# TFT_4_0-inch_OTM8009A_Sch.net
KiCad netlist of a schematic drawn in Altium Designer
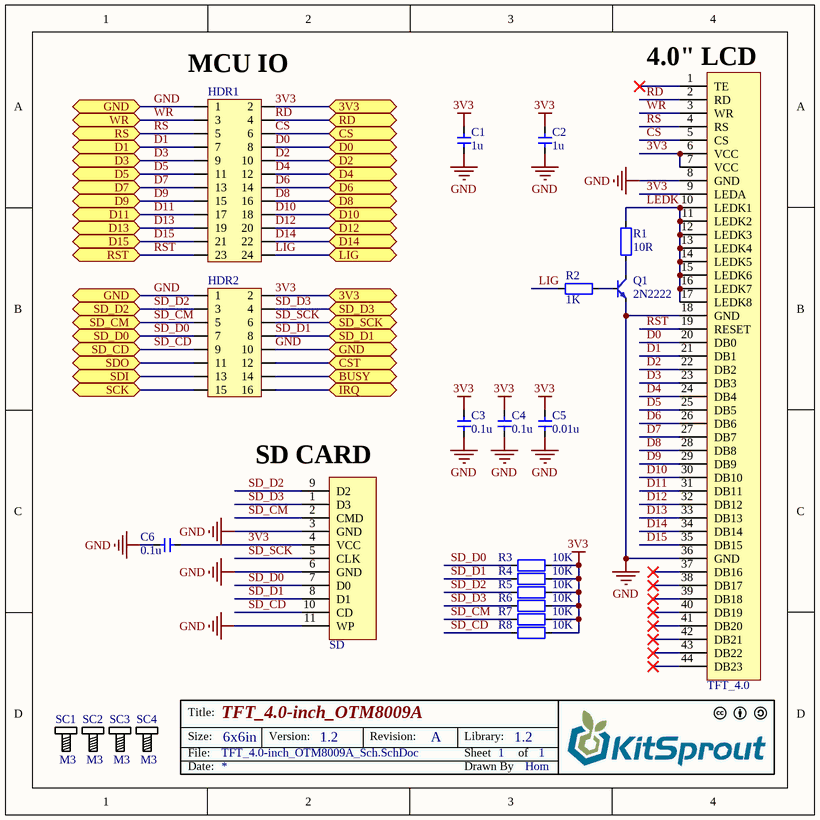
[diagram p0: TFT_4.0-inch_OTM8009A_Sch.SchDoc]

(export (version "E")
  (design (tool "Eeschema 10.0.6"))
  (components
    (comp (ref "C1")
      (value "1u")
      (footprint "PCB_PassiveCap:CAP_0603")
      (description "Capacitor")
      (fields (field (name "Comment") "Cap_0603"))
      (libsource (lib "SCH_Passive") (part "Cap_0603"))
    )
    (comp (ref "C2")
      (value "1u")
      (footprint "PCB_PassiveCap:CAP_0603")
      (description "Capacitor")
      (fields (field (name "Comment") "Cap_0603"))
      (libsource (lib "SCH_Passive") (part "Cap_0603"))
    )
    (comp (ref "C3")
      (value "0.1u")
      (footprint "PCB_PassiveCap:CAP_0603")
      (description "Capacitor")
      (fields (field (name "Comment") "Cap_0603"))
      (libsource (lib "SCH_Passive") (part "Cap_0603"))
    )
    (comp (ref "C4")
      (value "0.1u")
      (footprint "PCB_PassiveCap:CAP_0603")
      (description "Capacitor")
      (fields (field (name "Comment") "Cap_0603"))
      (libsource (lib "SCH_Passive") (part "Cap_0603"))
    )
    (comp (ref "C5")
      (value "0.01u")
      (footprint "PCB_PassiveCap:CAP_0603")
      (description "Capacitor")
      (fields (field (name "Comment") "Cap_0603"))
      (libsource (lib "SCH_Passive") (part "Cap_0603"))
    )
    (comp (ref "C6")
      (value "0.1u")
      (footprint "PCB_PassiveCap:CAP_0603")
      (description "Capacitor")
      (fields (field (name "Comment") "Cap_0603"))
      (libsource (lib "SCH_Passive") (part "Cap_0603"))
    )
    (comp (ref "HDR1")
      (value "HDR2x12_2.54")
      (footprint "PCB_ConnectorHDR:HDR2X12_2.54_180F")
      (description "Header")
      (libsource (lib "SCH_ConnectorHDR") (part "HDR2x12_2.54"))
    )
    (comp (ref "HDR2")
      (value "HDR2x8_2.54")
      (footprint "PCB_ConnectorHDR:HDR2X8_2.54_180F")
      (description "Header")
      (libsource (lib "SCH_ConnectorHDR") (part "HDR2x8_2.54"))
    )
    (comp (ref "Q1")
      (value "BJT_NPN")
      (footprint "PCB_IntegratedCircuit:SOT23-3")
      (description "Transistor")
      (fields (field (name "ALTIUM_UNNAMED_1") "2N2222"))
      (libsource (lib "SCH_Active") (part "BJT_NPN"))
    )
    (comp (ref "R1")
      (value "10R")
      (footprint "PCB_PassiveRes:RES_0603")
      (description "Resistor")
      (fields (field (name "Comment") "Res_0603"))
      (libsource (lib "SCH_Passive") (part "Res_0603"))
    )
    (comp (ref "R2")
      (value "1K")
      (footprint "PCB_PassiveRes:RES_0603")
      (description "Resistor")
      (fields (field (name "Comment") "Res_0603"))
      (libsource (lib "") (part "Res_0603_1"))
    )
    (comp (ref "R3")
      (value "10K")
      (footprint "PCB_PassiveRes:RES_0603")
      (description "Resistor")
      (fields (field (name "Comment") "Res_0603"))
      (libsource (lib "") (part "Res_0603_1"))
    )
    (comp (ref "R4")
      (value "10K")
      (footprint "PCB_PassiveRes:RES_0603")
      (description "Resistor")
      (fields (field (name "Comment") "Res_0603"))
      (libsource (lib "") (part "Res_0603_1"))
    )
    (comp (ref "R5")
      (value "10K")
      (footprint "PCB_PassiveRes:RES_0603")
      (description "Resistor")
      (fields (field (name "Comment") "Res_0603"))
      (libsource (lib "") (part "Res_0603_1"))
    )
    (comp (ref "R6")
      (value "10K")
      (footprint "PCB_PassiveRes:RES_0603")
      (description "Resistor")
      (fields (field (name "Comment") "Res_0603"))
      (libsource (lib "") (part "Res_0603_1"))
    )
    (comp (ref "R7")
      (value "10K")
      (footprint "PCB_PassiveRes:RES_0603")
      (description "Resistor")
      (fields (field (name "Comment") "Res_0603"))
      (libsource (lib "") (part "Res_0603_1"))
    )
    (comp (ref "R8")
      (value "10K")
      (footprint "PCB_PassiveRes:RES_0603")
      (description "Resistor")
      (fields (field (name "Comment") "Res_0603"))
      (libsource (lib "") (part "Res_0603_1"))
    )
    (comp (ref "SC1")
      (value "M3")
      (footprint "PCB_Mechanical:SCRREW_M3")
      (description "Screw")
      (libsource (lib "SCH_Mechanical") (part "Screw_M3"))
    )
    (comp (ref "SC2")
      (value "M3")
      (footprint "PCB_Mechanical:SCRREW_M3")
      (description "Screw")
      (libsource (lib "SCH_Mechanical") (part "Screw_M3"))
    )
    (comp (ref "SC3")
      (value "M3")
      (footprint "PCB_Mechanical:SCRREW_M3")
      (description "Screw")
      (libsource (lib "SCH_Mechanical") (part "Screw_M3"))
    )
    (comp (ref "SC4")
      (value "M3")
      (footprint "PCB_Mechanical:SCRREW_M3")
      (description "Screw")
      (libsource (lib "SCH_Mechanical") (part "Screw_M3"))
    )
    (comp (ref "SD")
      (value "SD_Card")
      (footprint "PCB_SDCard:SD_Card_1")
      (description "SD")
      (libsource (lib "SCH_SDCard") (part "SD_Card"))
    )
    (comp (ref "TFT_4.0")
      (value "TFT_4.0_OTM8009A")
      (footprint "PCB_Module:TFT_4.0_800x480_OTM8009A")
      (description "TFT")
      (libsource (lib "SCH_Module") (part "TFT_4.0_OTM8009A"))
    )
  )
  (nets
    (net (code "1") (name "/BUSY") (class "Default")
      (node (ref "HDR2") (pin "14") (pinfunction "14_14") (pintype "passive"))
    )
    (net (code "2") (name "/CS") (class "Default")
      (node (ref "HDR1") (pin "6") (pinfunction "6_6") (pintype "passive"))
      (node (ref "TFT_4.0") (pin "5") (pinfunction "CS_5") (pintype "passive"))
    )
    (net (code "3") (name "/CST") (class "Default")
      (node (ref "HDR2") (pin "12") (pinfunction "12_12") (pintype "passive"))
    )
    (net (code "4") (name "/D0") (class "Default")
      (node (ref "HDR1") (pin "8") (pinfunction "8_8") (pintype "passive"))
      (node (ref "TFT_4.0") (pin "20") (pinfunction "DB0_20") (pintype "passive"))
    )
    (net (code "5") (name "/D1") (class "Default")
      (node (ref "HDR1") (pin "7") (pinfunction "7_7") (pintype "passive"))
      (node (ref "TFT_4.0") (pin "21") (pinfunction "DB1_21") (pintype "passive"))
    )
    (net (code "6") (name "/D2") (class "Default")
      (node (ref "HDR1") (pin "10") (pinfunction "10_10") (pintype "passive"))
      (node (ref "TFT_4.0") (pin "22") (pinfunction "DB2_22") (pintype "passive"))
    )
    (net (code "7") (name "/D3") (class "Default")
      (node (ref "HDR1") (pin "9") (pinfunction "9_9") (pintype "passive"))
      (node (ref "TFT_4.0") (pin "23") (pinfunction "DB3_23") (pintype "passive"))
    )
    (net (code "8") (name "/D4") (class "Default")
      (node (ref "HDR1") (pin "12") (pinfunction "12_12") (pintype "passive"))
      (node (ref "TFT_4.0") (pin "24") (pinfunction "DB4_24") (pintype "passive"))
    )
    (net (code "9") (name "/D5") (class "Default")
      (node (ref "HDR1") (pin "11") (pinfunction "11_11") (pintype "passive"))
      (node (ref "TFT_4.0") (pin "25") (pinfunction "DB5_25") (pintype "passive"))
    )
    (net (code "10") (name "/D6") (class "Default")
      (node (ref "HDR1") (pin "14") (pinfunction "14_14") (pintype "passive"))
      (node (ref "TFT_4.0") (pin "26") (pinfunction "DB6_26") (pintype "passive"))
    )
    (net (code "11") (name "/D7") (class "Default")
      (node (ref "HDR1") (pin "13") (pinfunction "13_13") (pintype "passive"))
      (node (ref "TFT_4.0") (pin "27") (pinfunction "DB7_27") (pintype "passive"))
    )
    (net (code "12") (name "/D8") (class "Default")
      (node (ref "HDR1") (pin "16") (pinfunction "16_16") (pintype "passive"))
      (node (ref "TFT_4.0") (pin "28") (pinfunction "DB8_28") (pintype "passive"))
    )
    (net (code "13") (name "/D9") (class "Default")
      (node (ref "HDR1") (pin "15") (pinfunction "15_15") (pintype "passive"))
      (node (ref "TFT_4.0") (pin "29") (pinfunction "DB9_29") (pintype "passive"))
    )
    (net (code "14") (name "/D10") (class "Default")
      (node (ref "HDR1") (pin "18") (pinfunction "18_18") (pintype "passive"))
      (node (ref "TFT_4.0") (pin "30") (pinfunction "DB10_30") (pintype "passive"))
    )
    (net (code "15") (name "/D11") (class "Default")
      (node (ref "HDR1") (pin "17") (pinfunction "17_17") (pintype "passive"))
      (node (ref "TFT_4.0") (pin "31") (pinfunction "DB11_31") (pintype "passive"))
    )
    (net (code "16") (name "/D12") (class "Default")
      (node (ref "HDR1") (pin "20") (pinfunction "20_20") (pintype "passive"))
      (node (ref "TFT_4.0") (pin "32") (pinfunction "DB12_32") (pintype "passive"))
    )
    (net (code "17") (name "/D13") (class "Default")
      (node (ref "HDR1") (pin "19") (pinfunction "19_19") (pintype "passive"))
      (node (ref "TFT_4.0") (pin "33") (pinfunction "DB13_33") (pintype "passive"))
    )
    (net (code "18") (name "/D14") (class "Default")
      (node (ref "HDR1") (pin "22") (pinfunction "22_22") (pintype "passive"))
      (node (ref "TFT_4.0") (pin "34") (pinfunction "DB14_34") (pintype "passive"))
    )
    (net (code "19") (name "/D15") (class "Default")
      (node (ref "HDR1") (pin "21") (pinfunction "21_21") (pintype "passive"))
      (node (ref "TFT_4.0") (pin "35") (pinfunction "DB15_35") (pintype "passive"))
    )
    (net (code "20") (name "/IRQ") (class "Default")
      (node (ref "HDR2") (pin "16") (pinfunction "16_16") (pintype "passive"))
    )
    (net (code "21") (name "/LEDK") (class "Default")
      (node (ref "R1") (pin "2") (pinfunction "2_2") (pintype "passive"))
      (node (ref "TFT_4.0") (pin "10") (pinfunction "LEDK1_10") (pintype "passive"))
      (node (ref "TFT_4.0") (pin "11") (pinfunction "LEDK2_11") (pintype "passive"))
      (node (ref "TFT_4.0") (pin "12") (pinfunction "LEDK3_12") (pintype "passive"))
      (node (ref "TFT_4.0") (pin "13") (pinfunction "LEDK4_13") (pintype "passive"))
      (node (ref "TFT_4.0") (pin "14") (pinfunction "LEDK5_14") (pintype "passive"))
      (node (ref "TFT_4.0") (pin "15") (pinfunction "LEDK6_15") (pintype "passive"))
      (node (ref "TFT_4.0") (pin "16") (pinfunction "LEDK7_16") (pintype "passive"))
      (node (ref "TFT_4.0") (pin "17") (pinfunction "LEDK8_17") (pintype "passive"))
    )
    (net (code "22") (name "/LIG") (class "Default")
      (node (ref "HDR1") (pin "24") (pinfunction "24_24") (pintype "passive"))
      (node (ref "R2") (pin "2") (pinfunction "2_2") (pintype "passive"))
    )
    (net (code "23") (name "/RD") (class "Default")
      (node (ref "HDR1") (pin "4") (pinfunction "4_4") (pintype "passive"))
      (node (ref "TFT_4.0") (pin "2") (pinfunction "RD_2") (pintype "passive"))
    )
    (net (code "24") (name "/RS") (class "Default")
      (node (ref "HDR1") (pin "5") (pinfunction "5_5") (pintype "passive"))
      (node (ref "TFT_4.0") (pin "4") (pinfunction "RS_4") (pintype "passive"))
    )
    (net (code "25") (name "/RST") (class "Default")
      (node (ref "HDR1") (pin "23") (pinfunction "23_23") (pintype "passive"))
      (node (ref "TFT_4.0") (pin "19") (pinfunction "RESET_19") (pintype "passive"))
    )
    (net (code "26") (name "/SCK") (class "Default")
      (node (ref "HDR2") (pin "15") (pinfunction "15_15") (pintype "passive"))
    )
    (net (code "27") (name "/SDI") (class "Default")
      (node (ref "HDR2") (pin "13") (pinfunction "13_13") (pintype "passive"))
    )
    (net (code "28") (name "/SDO") (class "Default")
      (node (ref "HDR2") (pin "11") (pinfunction "11_11") (pintype "passive"))
    )
    (net (code "29") (name "/SD_CD") (class "Default")
      (node (ref "HDR2") (pin "9") (pinfunction "9_9") (pintype "passive"))
      (node (ref "R8") (pin "2") (pinfunction "2_2") (pintype "passive"))
      (node (ref "SD") (pin "10") (pinfunction "CD_10") (pintype "passive"))
    )
    (net (code "30") (name "/SD_CM") (class "Default")
      (node (ref "HDR2") (pin "5") (pinfunction "5_5") (pintype "passive"))
      (node (ref "R7") (pin "2") (pinfunction "2_2") (pintype "passive"))
      (node (ref "SD") (pin "2") (pinfunction "CMD_2") (pintype "passive"))
    )
    (net (code "31") (name "/SD_D0") (class "Default")
      (node (ref "HDR2") (pin "7") (pinfunction "7_7") (pintype "passive"))
      (node (ref "R3") (pin "2") (pinfunction "2_2") (pintype "passive"))
      (node (ref "SD") (pin "7") (pinfunction "D0_7") (pintype "passive"))
    )
    (net (code "32") (name "/SD_D1") (class "Default")
      (node (ref "HDR2") (pin "8") (pinfunction "8_8") (pintype "passive"))
      (node (ref "R4") (pin "2") (pinfunction "2_2") (pintype "passive"))
      (node (ref "SD") (pin "8") (pinfunction "D1_8") (pintype "passive"))
    )
    (net (code "33") (name "/SD_D2") (class "Default")
      (node (ref "HDR2") (pin "3") (pinfunction "3_3") (pintype "passive"))
      (node (ref "R5") (pin "2") (pinfunction "2_2") (pintype "passive"))
      (node (ref "SD") (pin "9") (pinfunction "D2_9") (pintype "passive"))
    )
    (net (code "34") (name "/SD_D3") (class "Default")
      (node (ref "HDR2") (pin "4") (pinfunction "4_4") (pintype "passive"))
      (node (ref "R6") (pin "2") (pinfunction "2_2") (pintype "passive"))
      (node (ref "SD") (pin "1") (pinfunction "D3_1") (pintype "passive"))
    )
    (net (code "35") (name "/SD_SCK") (class "Default")
      (node (ref "HDR2") (pin "6") (pinfunction "6_6") (pintype "passive"))
      (node (ref "SD") (pin "5") (pinfunction "CLK_5") (pintype "passive"))
    )
    (net (code "36") (name "/WR") (class "Default")
      (node (ref "HDR1") (pin "3") (pinfunction "3_3") (pintype "passive"))
      (node (ref "TFT_4.0") (pin "3") (pinfunction "WR_3") (pintype "passive"))
    )
    (net (code "37") (name "3V3") (class "Default")
      (node (ref "C1") (pin "2") (pinfunction "2_2") (pintype "passive"))
      (node (ref "C2") (pin "2") (pinfunction "2_2") (pintype "passive"))
      (node (ref "C3") (pin "2") (pinfunction "2_2") (pintype "passive"))
      (node (ref "C4") (pin "2") (pinfunction "2_2") (pintype "passive"))
      (node (ref "C5") (pin "2") (pinfunction "2_2") (pintype "passive"))
      (node (ref "C6") (pin "1") (pinfunction "1_1") (pintype "passive"))
      (node (ref "HDR1") (pin "2") (pinfunction "2_2") (pintype "passive"))
      (node (ref "HDR2") (pin "2") (pinfunction "2_2") (pintype "passive"))
      (node (ref "R3") (pin "1") (pinfunction "1_1") (pintype "passive"))
      (node (ref "R4") (pin "1") (pinfunction "1_1") (pintype "passive"))
      (node (ref "R5") (pin "1") (pinfunction "1_1") (pintype "passive"))
      (node (ref "R6") (pin "1") (pinfunction "1_1") (pintype "passive"))
      (node (ref "R7") (pin "1") (pinfunction "1_1") (pintype "passive"))
      (node (ref "R8") (pin "1") (pinfunction "1_1") (pintype "passive"))
      (node (ref "SD") (pin "4") (pinfunction "VCC_4") (pintype "passive"))
      (node (ref "TFT_4.0") (pin "6") (pinfunction "VCC_6") (pintype "passive"))
      (node (ref "TFT_4.0") (pin "7") (pinfunction "VCC_7") (pintype "passive"))
      (node (ref "TFT_4.0") (pin "9") (pinfunction "LEDA_9") (pintype "passive"))
    )
    (net (code "38") (name "GND") (class "Default")
      (node (ref "C1") (pin "1") (pinfunction "1_1") (pintype "passive"))
      (node (ref "C2") (pin "1") (pinfunction "1_1") (pintype "passive"))
      (node (ref "C3") (pin "1") (pinfunction "1_1") (pintype "passive"))
      (node (ref "C4") (pin "1") (pinfunction "1_1") (pintype "passive"))
      (node (ref "C5") (pin "1") (pinfunction "1_1") (pintype "passive"))
      (node (ref "C6") (pin "2") (pinfunction "2_2") (pintype "passive"))
      (node (ref "HDR1") (pin "1") (pinfunction "1_1") (pintype "passive"))
      (node (ref "HDR2") (pin "1") (pinfunction "1_1") (pintype "passive"))
      (node (ref "HDR2") (pin "10") (pinfunction "10_10") (pintype "passive"))
      (node (ref "Q1") (pin "2") (pinfunction "E_2") (pintype "passive"))
      (node (ref "SD") (pin "11") (pinfunction "WP_11") (pintype "passive"))
      (node (ref "SD") (pin "3") (pinfunction "GND_3") (pintype "passive"))
      (node (ref "SD") (pin "6") (pinfunction "GND_6") (pintype "passive"))
      (node (ref "TFT_4.0") (pin "18") (pinfunction "GND_18") (pintype "passive"))
      (node (ref "TFT_4.0") (pin "36") (pinfunction "GND_36") (pintype "passive"))
      (node (ref "TFT_4.0") (pin "8") (pinfunction "GND_8") (pintype "passive"))
    )
    (net (code "39") (name "Net-(Q1-B)") (class "Default")
      (node (ref "Q1") (pin "1") (pinfunction "B_1") (pintype "passive"))
      (node (ref "R2") (pin "1") (pinfunction "1_1") (pintype "passive"))
    )
    (net (code "40") (name "Net-(Q1-C)") (class "Default")
      (node (ref "Q1") (pin "3") (pinfunction "C_3") (pintype "passive"))
      (node (ref "R1") (pin "1") (pinfunction "1_1") (pintype "passive"))
    )
    (net (code "41") (name "unconnected-(TFT_4.0-DB16-Pad37)") (class "Default")
      (node (ref "TFT_4.0") (pin "37") (pinfunction "DB16_37") (pintype "passive+no_connect"))
    )
    (net (code "42") (name "unconnected-(TFT_4.0-DB17-Pad38)") (class "Default")
      (node (ref "TFT_4.0") (pin "38") (pinfunction "DB17_38") (pintype "passive+no_connect"))
    )
    (net (code "43") (name "unconnected-(TFT_4.0-DB18-Pad39)") (class "Default")
      (node (ref "TFT_4.0") (pin "39") (pinfunction "DB18_39") (pintype "passive+no_connect"))
    )
    (net (code "44") (name "unconnected-(TFT_4.0-DB19-Pad40)") (class "Default")
      (node (ref "TFT_4.0") (pin "40") (pinfunction "DB19_40") (pintype "passive+no_connect"))
    )
    (net (code "45") (name "unconnected-(TFT_4.0-DB20-Pad41)") (class "Default")
      (node (ref "TFT_4.0") (pin "41") (pinfunction "DB20_41") (pintype "passive+no_connect"))
    )
    (net (code "46") (name "unconnected-(TFT_4.0-DB21-Pad42)") (class "Default")
      (node (ref "TFT_4.0") (pin "42") (pinfunction "DB21_42") (pintype "passive+no_connect"))
    )
    (net (code "47") (name "unconnected-(TFT_4.0-DB22-Pad43)") (class "Default")
      (node (ref "TFT_4.0") (pin "43") (pinfunction "DB22_43") (pintype "passive+no_connect"))
    )
    (net (code "48") (name "unconnected-(TFT_4.0-DB23-Pad44)") (class "Default")
      (node (ref "TFT_4.0") (pin "44") (pinfunction "DB23_44") (pintype "passive+no_connect"))
    )
    (net (code "49") (name "unconnected-(TFT_4.0-TE-Pad1)") (class "Default")
      (node (ref "TFT_4.0") (pin "1") (pinfunction "TE_1") (pintype "passive+no_connect"))
    )
  )
)
